# MQ135.net
KiCad netlist of a schematic drawn in Altium Designer
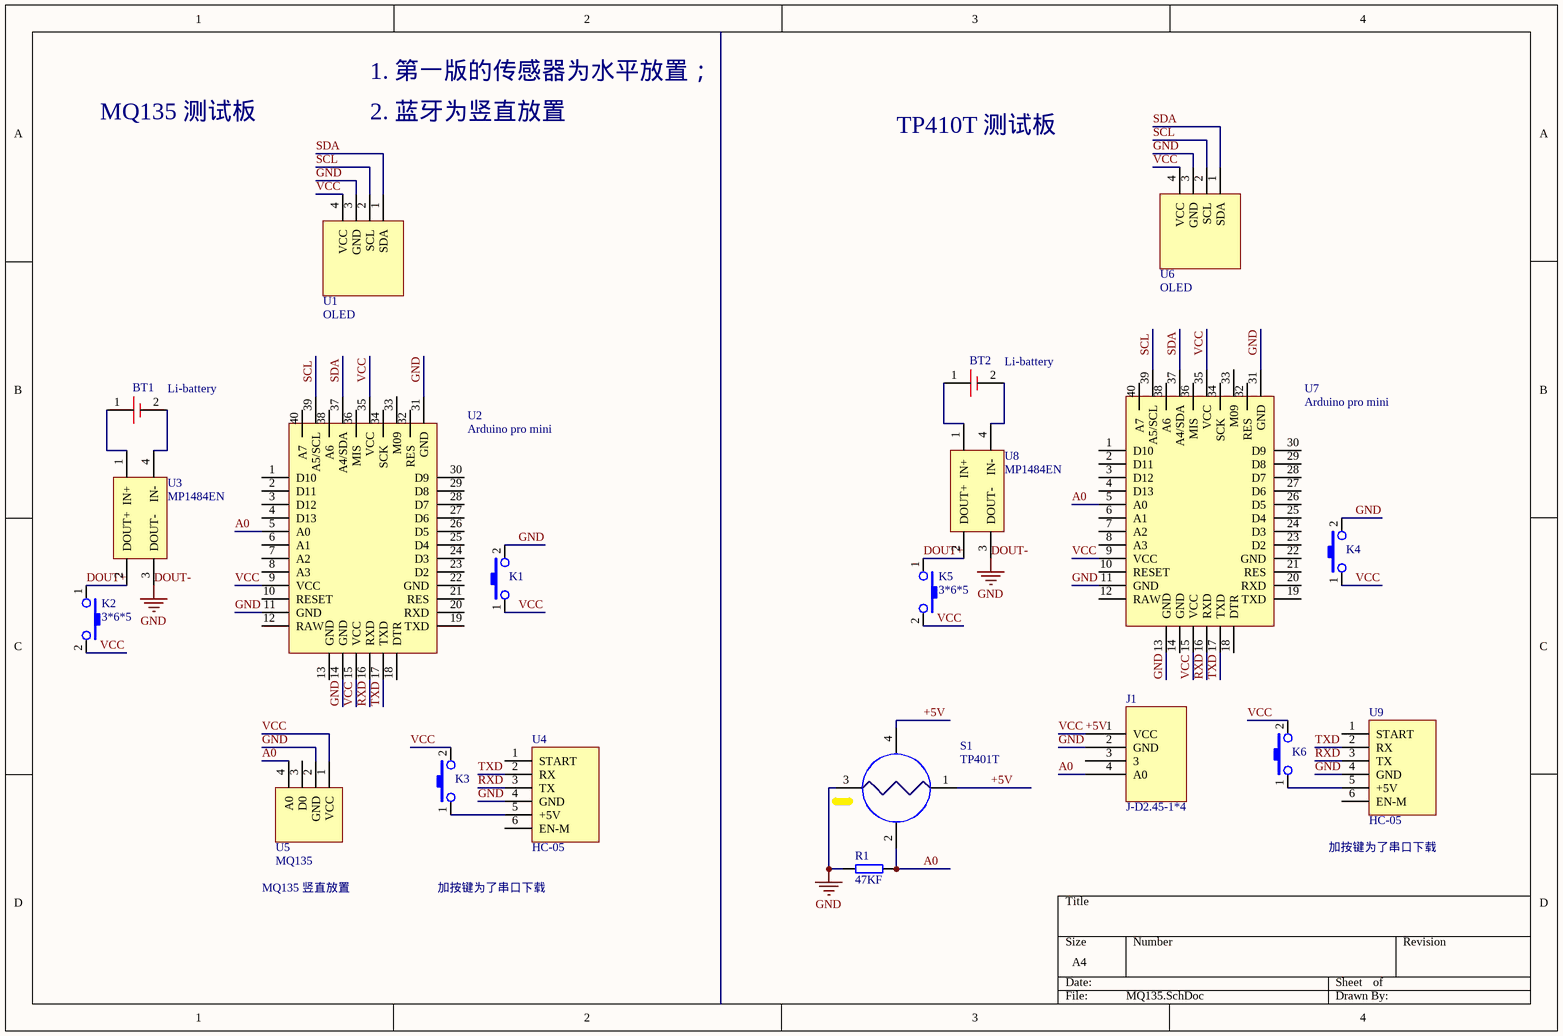
[diagram p0: MQ135.SchDoc]

(export (version "E")
  (design (tool "Eeschema 10.0.6"))
  (components
    (comp (ref "BT1")
      (value "Li-battery")
      (footprint "LIR2032")
      (description "纽扣电池LIR2023")
      (libsource (lib "Others") (part "Li-batttery"))
    )
    (comp (ref "BT2")
      (value "Li-battery")
      (footprint "LIR2032")
      (description "纽扣电池LIR2023")
      (libsource (lib "Others") (part "Li-batttery"))
    )
    (comp (ref "J1")
      (value "J-D2.45-1*4")
      (footprint "D2.54-1*4P")
      (description "TP401T 气敏传感器")
      (libsource (lib "Connector") (part "J-D2.54-1*4单排排母_1"))
    )
    (comp (ref "K1")
      (value "3*6*5")
      (footprint "S-K3*6")
      (description "贴片-卧式轻触开关")
      (libsource (lib "Key") (part "3*6*5"))
    )
    (comp (ref "K2")
      (value "3*6*5")
      (footprint "S-K3*6")
      (description "贴片-卧式轻触开关")
      (libsource (lib "Key") (part "3*6*5"))
    )
    (comp (ref "K3")
      (value "3*6*5")
      (footprint "S-K3*6")
      (description "贴片-卧式轻触开关")
      (libsource (lib "Key") (part "3*6*5"))
    )
    (comp (ref "K4")
      (value "3*6*5")
      (footprint "S-K3*6")
      (description "贴片-卧式轻触开关")
      (libsource (lib "Key") (part "3*6*5"))
    )
    (comp (ref "K5")
      (value "3*6*5")
      (footprint "S-K3*6")
      (description "贴片-卧式轻触开关")
      (libsource (lib "Key") (part "3*6*5"))
    )
    (comp (ref "K6")
      (value "3*6*5")
      (footprint "S-K3*6")
      (description "贴片-卧式轻触开关")
      (libsource (lib "Key") (part "3*6*5"))
    )
    (comp (ref "R1")
      (value "47KF")
      (footprint "R0603")
      (description "贴片电阻-通用")
      (libsource (lib "Resistor") (part "R0603-47KF"))
    )
    (comp (ref "S1") (value "TP401T") (description "异味传感器") (libsource (lib "Module") (part "TP401T")))
    (comp (ref "U1") (value "OLED") (description "OLED IIC屏幕显示") (libsource (lib "Module") (part "OLED")))
    (comp (ref "U2")
      (value "Arduino pro mini")
      (description "Pro mini")
      (libsource (lib "Module") (part "Arduino pro mini"))
    )
    (comp (ref "U3")
      (value "MP1484EN")
      (description "MP1484EN 稳压模块 5V")
      (libsource (lib "Module") (part "DC稳压模块"))
    )
    (comp (ref "U4")
      (value "HC-05")
      (description "Bluetooth model")
      (libsource (lib "Module") (part "HC-05"))
    )
    (comp (ref "U5") (value "MQ135") (description "气敏传感器") (libsource (lib "Module") (part "MQ135")))
    (comp (ref "U6") (value "OLED") (description "OLED IIC屏幕显示") (libsource (lib "Module") (part "OLED")))
    (comp (ref "U7")
      (value "Arduino pro mini")
      (description "Pro mini")
      (libsource (lib "Module") (part "Arduino pro mini"))
    )
    (comp (ref "U8")
      (value "MP1484EN")
      (description "MP1484EN 稳压模块 5V")
      (libsource (lib "Module") (part "DC稳压模块"))
    )
    (comp (ref "U9")
      (value "HC-05")
      (description "Bluetooth model")
      (libsource (lib "Module") (part "HC-05"))
    )
  )
  (nets
    (net (code "1") (name "/+5V") (class "Default")
      (node (ref "J1") (pin "1") (pinfunction "VCC_1") (pintype "passive"))
      (node (ref "K1") (pin "1") (pinfunction "1_1") (pintype "passive"))
      (node (ref "K2") (pin "2") (pinfunction "2_2") (pintype "passive"))
      (node (ref "K3") (pin "2") (pinfunction "2_2") (pintype "passive"))
      (node (ref "K4") (pin "1") (pinfunction "1_1") (pintype "passive"))
      (node (ref "K5") (pin "2") (pinfunction "2_2") (pintype "passive"))
      (node (ref "K6") (pin "2") (pinfunction "2_2") (pintype "passive"))
      (node (ref "S1") (pin "1") (pinfunction "1_1") (pintype "passive"))
      (node (ref "S1") (pin "4") (pinfunction "4_4") (pintype "passive"))
      (node (ref "U1") (pin "4") (pinfunction "VCC_4") (pintype "passive"))
      (node (ref "U2") (pin "15") (pinfunction "VCC_15") (pintype "passive"))
      (node (ref "U2") (pin "35") (pinfunction "VCC_35") (pintype "passive"))
      (node (ref "U2") (pin "9") (pinfunction "VCC_9") (pintype "passive"))
      (node (ref "U5") (pin "1") (pinfunction "VCC_1") (pintype "passive"))
      (node (ref "U6") (pin "4") (pinfunction "VCC_4") (pintype "passive"))
      (node (ref "U7") (pin "15") (pinfunction "VCC_15") (pintype "passive"))
      (node (ref "U7") (pin "35") (pinfunction "VCC_35") (pintype "passive"))
      (node (ref "U7") (pin "9") (pinfunction "VCC_9") (pintype "passive"))
    )
    (net (code "2") (name "/A0") (class "Default")
      (node (ref "J1") (pin "4") (pinfunction "A0_4") (pintype "passive"))
      (node (ref "R1") (pin "1") (pinfunction "1_1") (pintype "passive"))
      (node (ref "S1") (pin "2") (pinfunction "2_2") (pintype "passive"))
      (node (ref "U2") (pin "5") (pinfunction "A0_5") (pintype "passive"))
      (node (ref "U5") (pin "4") (pinfunction "A0_4") (pintype "passive"))
      (node (ref "U7") (pin "5") (pinfunction "A0_5") (pintype "passive"))
    )
    (net (code "3") (name "/DOUT+") (class "Default")
      (node (ref "K2") (pin "1") (pinfunction "1_1") (pintype "passive"))
      (node (ref "K5") (pin "1") (pinfunction "1_1") (pintype "passive"))
      (node (ref "U3") (pin "2") (pinfunction "DOUT+_2") (pintype "passive"))
      (node (ref "U8") (pin "2") (pinfunction "DOUT+_2") (pintype "passive"))
    )
    (net (code "4") (name "/RXD") (class "Default")
      (node (ref "U2") (pin "16") (pinfunction "RXD_16") (pintype "passive"))
      (node (ref "U4") (pin "3") (pinfunction "TX_3") (pintype "passive"))
      (node (ref "U7") (pin "16") (pinfunction "RXD_16") (pintype "passive"))
      (node (ref "U9") (pin "3") (pinfunction "TX_3") (pintype "passive"))
    )
    (net (code "5") (name "/SCL") (class "Default")
      (node (ref "U1") (pin "2") (pinfunction "SCL_2") (pintype "passive"))
      (node (ref "U2") (pin "39") (pinfunction "A5/SCL_39") (pintype "passive"))
      (node (ref "U6") (pin "2") (pinfunction "SCL_2") (pintype "passive"))
      (node (ref "U7") (pin "39") (pinfunction "A5/SCL_39") (pintype "passive"))
    )
    (net (code "6") (name "/SDA") (class "Default")
      (node (ref "U1") (pin "1") (pinfunction "SDA_1") (pintype "passive"))
      (node (ref "U2") (pin "37") (pinfunction "A4/SDA_37") (pintype "passive"))
      (node (ref "U6") (pin "1") (pinfunction "SDA_1") (pintype "passive"))
      (node (ref "U7") (pin "37") (pinfunction "A4/SDA_37") (pintype "passive"))
    )
    (net (code "7") (name "/TXD") (class "Default")
      (node (ref "U2") (pin "17") (pinfunction "TXD_17") (pintype "passive"))
      (node (ref "U4") (pin "2") (pinfunction "RX_2") (pintype "passive"))
      (node (ref "U7") (pin "17") (pinfunction "TXD_17") (pintype "passive"))
      (node (ref "U9") (pin "2") (pinfunction "RX_2") (pintype "passive"))
    )
    (net (code "8") (name "GND") (class "Default")
      (node (ref "J1") (pin "2") (pinfunction "GND_2") (pintype "passive"))
      (node (ref "K1") (pin "2") (pinfunction "2_2") (pintype "passive"))
      (node (ref "K4") (pin "2") (pinfunction "2_2") (pintype "passive"))
      (node (ref "R1") (pin "2") (pinfunction "2_2") (pintype "passive"))
      (node (ref "S1") (pin "3") (pinfunction "3_3") (pintype "passive"))
      (node (ref "U1") (pin "3") (pinfunction "GND_3") (pintype "passive"))
      (node (ref "U2") (pin "11") (pinfunction "GND_11") (pintype "passive"))
      (node (ref "U2") (pin "14") (pinfunction "GND_14") (pintype "passive"))
      (node (ref "U2") (pin "31") (pinfunction "GND_31") (pintype "passive"))
      (node (ref "U3") (pin "3") (pinfunction "DOUT-_3") (pintype "passive"))
      (node (ref "U4") (pin "4") (pinfunction "GND_4") (pintype "passive"))
      (node (ref "U5") (pin "2") (pinfunction "GND_2") (pintype "passive"))
      (node (ref "U6") (pin "3") (pinfunction "GND_3") (pintype "passive"))
      (node (ref "U7") (pin "11") (pinfunction "GND_11") (pintype "passive"))
      (node (ref "U7") (pin "13") (pinfunction "GND_13") (pintype "passive"))
      (node (ref "U7") (pin "31") (pinfunction "GND_31") (pintype "passive"))
      (node (ref "U8") (pin "3") (pinfunction "DOUT-_3") (pintype "passive"))
      (node (ref "U9") (pin "4") (pinfunction "GND_4") (pintype "passive"))
    )
    (net (code "9") (name "Net-(BT1-GND)") (class "Default")
      (node (ref "BT1") (pin "2") (pinfunction "GND_2") (pintype "passive"))
      (node (ref "U3") (pin "4") (pinfunction "IN-_4") (pintype "passive"))
    )
    (net (code "10") (name "Net-(BT1-VCC)") (class "Default")
      (node (ref "BT1") (pin "1") (pinfunction "VCC_1") (pintype "passive"))
      (node (ref "U3") (pin "1") (pinfunction "IN+_1") (pintype "passive"))
    )
    (net (code "11") (name "Net-(BT2-GND)") (class "Default")
      (node (ref "BT2") (pin "2") (pinfunction "GND_2") (pintype "passive"))
      (node (ref "U8") (pin "4") (pinfunction "IN-_4") (pintype "passive"))
    )
    (net (code "12") (name "Net-(BT2-VCC)") (class "Default")
      (node (ref "BT2") (pin "1") (pinfunction "VCC_1") (pintype "passive"))
      (node (ref "U8") (pin "1") (pinfunction "IN+_1") (pintype "passive"))
    )
    (net (code "13") (name "Net-(U4-+5V)") (class "Default")
      (node (ref "K3") (pin "1") (pinfunction "1_1") (pintype "passive"))
      (node (ref "U4") (pin "5") (pinfunction "+5V_5") (pintype "passive"))
    )
    (net (code "14") (name "Net-(U9-+5V)") (class "Default")
      (node (ref "K6") (pin "1") (pinfunction "1_1") (pintype "passive"))
      (node (ref "U9") (pin "5") (pinfunction "+5V_5") (pintype "passive"))
    )
    (net (code "15") (name "unconnected-(J1-Pad3)") (class "Default")
      (node (ref "J1") (pin "3") (pinfunction "3_3") (pintype "passive"))
    )
    (net (code "16") (name "unconnected-(U2-A1-Pad6)") (class "Default")
      (node (ref "U2") (pin "6") (pinfunction "A1_6") (pintype "passive"))
    )
    (net (code "17") (name "unconnected-(U2-A2-Pad7)") (class "Default")
      (node (ref "U2") (pin "7") (pinfunction "A2_7") (pintype "passive"))
    )
    (net (code "18") (name "unconnected-(U2-A3-Pad8)") (class "Default")
      (node (ref "U2") (pin "8") (pinfunction "A3_8") (pintype "passive"))
    )
    (net (code "19") (name "unconnected-(U2-A6-Pad38)") (class "Default")
      (node (ref "U2") (pin "38") (pinfunction "A6_38") (pintype "passive"))
    )
    (net (code "20") (name "unconnected-(U2-A7-Pad40)") (class "Default")
      (node (ref "U2") (pin "40") (pinfunction "A7_40") (pintype "passive"))
    )
    (net (code "21") (name "unconnected-(U2-D2-Pad23)") (class "Default")
      (node (ref "U2") (pin "23") (pinfunction "D2_23") (pintype "passive"))
    )
    (net (code "22") (name "unconnected-(U2-D3-Pad24)") (class "Default")
      (node (ref "U2") (pin "24") (pinfunction "D3_24") (pintype "passive"))
    )
    (net (code "23") (name "unconnected-(U2-D4-Pad25)") (class "Default")
      (node (ref "U2") (pin "25") (pinfunction "D4_25") (pintype "passive"))
    )
    (net (code "24") (name "unconnected-(U2-D5-Pad26)") (class "Default")
      (node (ref "U2") (pin "26") (pinfunction "D5_26") (pintype "passive"))
    )
    (net (code "25") (name "unconnected-(U2-D6-Pad27)") (class "Default")
      (node (ref "U2") (pin "27") (pinfunction "D6_27") (pintype "passive"))
    )
    (net (code "26") (name "unconnected-(U2-D7-Pad28)") (class "Default")
      (node (ref "U2") (pin "28") (pinfunction "D7_28") (pintype "passive"))
    )
    (net (code "27") (name "unconnected-(U2-D8-Pad29)") (class "Default")
      (node (ref "U2") (pin "29") (pinfunction "D8_29") (pintype "passive"))
    )
    (net (code "28") (name "unconnected-(U2-D9-Pad30)") (class "Default")
      (node (ref "U2") (pin "30") (pinfunction "D9_30") (pintype "passive"))
    )
    (net (code "29") (name "unconnected-(U2-D10-Pad1)") (class "Default")
      (node (ref "U2") (pin "1") (pinfunction "D10_1") (pintype "passive"))
    )
    (net (code "30") (name "unconnected-(U2-D11-Pad2)") (class "Default")
      (node (ref "U2") (pin "2") (pinfunction "D11_2") (pintype "passive"))
    )
    (net (code "31") (name "unconnected-(U2-D12-Pad3)") (class "Default")
      (node (ref "U2") (pin "3") (pinfunction "D12_3") (pintype "passive"))
    )
    (net (code "32") (name "unconnected-(U2-D13-Pad4)") (class "Default")
      (node (ref "U2") (pin "4") (pinfunction "D13_4") (pintype "passive"))
    )
    (net (code "33") (name "unconnected-(U2-DTR-Pad18)") (class "Default")
      (node (ref "U2") (pin "18") (pinfunction "DTR_18") (pintype "passive"))
    )
    (net (code "34") (name "unconnected-(U2-GND-Pad13)") (class "Default")
      (node (ref "U2") (pin "13") (pinfunction "GND_13") (pintype "passive"))
    )
    (net (code "35") (name "unconnected-(U2-GND-Pad22)") (class "Default")
      (node (ref "U2") (pin "22") (pinfunction "GND_22") (pintype "passive"))
    )
    (net (code "36") (name "unconnected-(U2-M09-Pad33)") (class "Default")
      (node (ref "U2") (pin "33") (pinfunction "M09_33") (pintype "passive"))
    )
    (net (code "37") (name "unconnected-(U2-MIS-Pad36)") (class "Default")
      (node (ref "U2") (pin "36") (pinfunction "MIS_36") (pintype "passive"))
    )
    (net (code "38") (name "unconnected-(U2-RAW-Pad12)") (class "Default")
      (node (ref "U2") (pin "12") (pinfunction "RAW_12") (pintype "passive"))
    )
    (net (code "39") (name "unconnected-(U2-RES-Pad21)") (class "Default")
      (node (ref "U2") (pin "21") (pinfunction "RES_21") (pintype "passive"))
    )
    (net (code "40") (name "unconnected-(U2-RES-Pad32)") (class "Default")
      (node (ref "U2") (pin "32") (pinfunction "RES_32") (pintype "passive"))
    )
    (net (code "41") (name "unconnected-(U2-RESET-Pad10)") (class "Default")
      (node (ref "U2") (pin "10") (pinfunction "RESET_10") (pintype "passive"))
    )
    (net (code "42") (name "unconnected-(U2-RXD-Pad20)") (class "Default")
      (node (ref "U2") (pin "20") (pinfunction "RXD_20") (pintype "passive"))
    )
    (net (code "43") (name "unconnected-(U2-SCK-Pad34)") (class "Default")
      (node (ref "U2") (pin "34") (pinfunction "SCK_34") (pintype "passive"))
    )
    (net (code "44") (name "unconnected-(U2-TXD-Pad19)") (class "Default")
      (node (ref "U2") (pin "19") (pinfunction "TXD_19") (pintype "passive"))
    )
    (net (code "45") (name "unconnected-(U4-EN-M-Pad6)") (class "Default")
      (node (ref "U4") (pin "6") (pinfunction "EN-M_6") (pintype "passive"))
    )
    (net (code "46") (name "unconnected-(U4-START-Pad1)") (class "Default")
      (node (ref "U4") (pin "1") (pinfunction "START_1") (pintype "passive"))
    )
    (net (code "47") (name "unconnected-(U5-D0-Pad3)") (class "Default")
      (node (ref "U5") (pin "3") (pinfunction "D0_3") (pintype "passive"))
    )
    (net (code "48") (name "unconnected-(U7-A1-Pad6)") (class "Default")
      (node (ref "U7") (pin "6") (pinfunction "A1_6") (pintype "passive"))
    )
    (net (code "49") (name "unconnected-(U7-A2-Pad7)") (class "Default")
      (node (ref "U7") (pin "7") (pinfunction "A2_7") (pintype "passive"))
    )
    (net (code "50") (name "unconnected-(U7-A3-Pad8)") (class "Default")
      (node (ref "U7") (pin "8") (pinfunction "A3_8") (pintype "passive"))
    )
    (net (code "51") (name "unconnected-(U7-A6-Pad38)") (class "Default")
      (node (ref "U7") (pin "38") (pinfunction "A6_38") (pintype "passive"))
    )
    (net (code "52") (name "unconnected-(U7-A7-Pad40)") (class "Default")
      (node (ref "U7") (pin "40") (pinfunction "A7_40") (pintype "passive"))
    )
    (net (code "53") (name "unconnected-(U7-D2-Pad23)") (class "Default")
      (node (ref "U7") (pin "23") (pinfunction "D2_23") (pintype "passive"))
    )
    (net (code "54") (name "unconnected-(U7-D3-Pad24)") (class "Default")
      (node (ref "U7") (pin "24") (pinfunction "D3_24") (pintype "passive"))
    )
    (net (code "55") (name "unconnected-(U7-D4-Pad25)") (class "Default")
      (node (ref "U7") (pin "25") (pinfunction "D4_25") (pintype "passive"))
    )
    (net (code "56") (name "unconnected-(U7-D5-Pad26)") (class "Default")
      (node (ref "U7") (pin "26") (pinfunction "D5_26") (pintype "passive"))
    )
    (net (code "57") (name "unconnected-(U7-D6-Pad27)") (class "Default")
      (node (ref "U7") (pin "27") (pinfunction "D6_27") (pintype "passive"))
    )
    (net (code "58") (name "unconnected-(U7-D7-Pad28)") (class "Default")
      (node (ref "U7") (pin "28") (pinfunction "D7_28") (pintype "passive"))
    )
    (net (code "59") (name "unconnected-(U7-D8-Pad29)") (class "Default")
      (node (ref "U7") (pin "29") (pinfunction "D8_29") (pintype "passive"))
    )
    (net (code "60") (name "unconnected-(U7-D9-Pad30)") (class "Default")
      (node (ref "U7") (pin "30") (pinfunction "D9_30") (pintype "passive"))
    )
    (net (code "61") (name "unconnected-(U7-D10-Pad1)") (class "Default")
      (node (ref "U7") (pin "1") (pinfunction "D10_1") (pintype "passive"))
    )
    (net (code "62") (name "unconnected-(U7-D11-Pad2)") (class "Default")
      (node (ref "U7") (pin "2") (pinfunction "D11_2") (pintype "passive"))
    )
    (net (code "63") (name "unconnected-(U7-D12-Pad3)") (class "Default")
      (node (ref "U7") (pin "3") (pinfunction "D12_3") (pintype "passive"))
    )
    (net (code "64") (name "unconnected-(U7-D13-Pad4)") (class "Default")
      (node (ref "U7") (pin "4") (pinfunction "D13_4") (pintype "passive"))
    )
    (net (code "65") (name "unconnected-(U7-DTR-Pad18)") (class "Default")
      (node (ref "U7") (pin "18") (pinfunction "DTR_18") (pintype "passive"))
    )
    (net (code "66") (name "unconnected-(U7-GND-Pad14)") (class "Default")
      (node (ref "U7") (pin "14") (pinfunction "GND_14") (pintype "passive"))
    )
    (net (code "67") (name "unconnected-(U7-GND-Pad22)") (class "Default")
      (node (ref "U7") (pin "22") (pinfunction "GND_22") (pintype "passive"))
    )
    (net (code "68") (name "unconnected-(U7-M09-Pad33)") (class "Default")
      (node (ref "U7") (pin "33") (pinfunction "M09_33") (pintype "passive"))
    )
    (net (code "69") (name "unconnected-(U7-MIS-Pad36)") (class "Default")
      (node (ref "U7") (pin "36") (pinfunction "MIS_36") (pintype "passive"))
    )
    (net (code "70") (name "unconnected-(U7-RAW-Pad12)") (class "Default")
      (node (ref "U7") (pin "12") (pinfunction "RAW_12") (pintype "passive"))
    )
    (net (code "71") (name "unconnected-(U7-RES-Pad21)") (class "Default")
      (node (ref "U7") (pin "21") (pinfunction "RES_21") (pintype "passive"))
    )
    (net (code "72") (name "unconnected-(U7-RES-Pad32)") (class "Default")
      (node (ref "U7") (pin "32") (pinfunction "RES_32") (pintype "passive"))
    )
    (net (code "73") (name "unconnected-(U7-RESET-Pad10)") (class "Default")
      (node (ref "U7") (pin "10") (pinfunction "RESET_10") (pintype "passive"))
    )
    (net (code "74") (name "unconnected-(U7-RXD-Pad20)") (class "Default")
      (node (ref "U7") (pin "20") (pinfunction "RXD_20") (pintype "passive"))
    )
    (net (code "75") (name "unconnected-(U7-SCK-Pad34)") (class "Default")
      (node (ref "U7") (pin "34") (pinfunction "SCK_34") (pintype "passive"))
    )
    (net (code "76") (name "unconnected-(U7-TXD-Pad19)") (class "Default")
      (node (ref "U7") (pin "19") (pinfunction "TXD_19") (pintype "passive"))
    )
    (net (code "77") (name "unconnected-(U9-EN-M-Pad6)") (class "Default")
      (node (ref "U9") (pin "6") (pinfunction "EN-M_6") (pintype "passive"))
    )
    (net (code "78") (name "unconnected-(U9-START-Pad1)") (class "Default")
      (node (ref "U9") (pin "1") (pinfunction "START_1") (pintype "passive"))
    )
  )
)
